# sy8502.net
KiCad netlist of a schematic drawn in Altium Designer
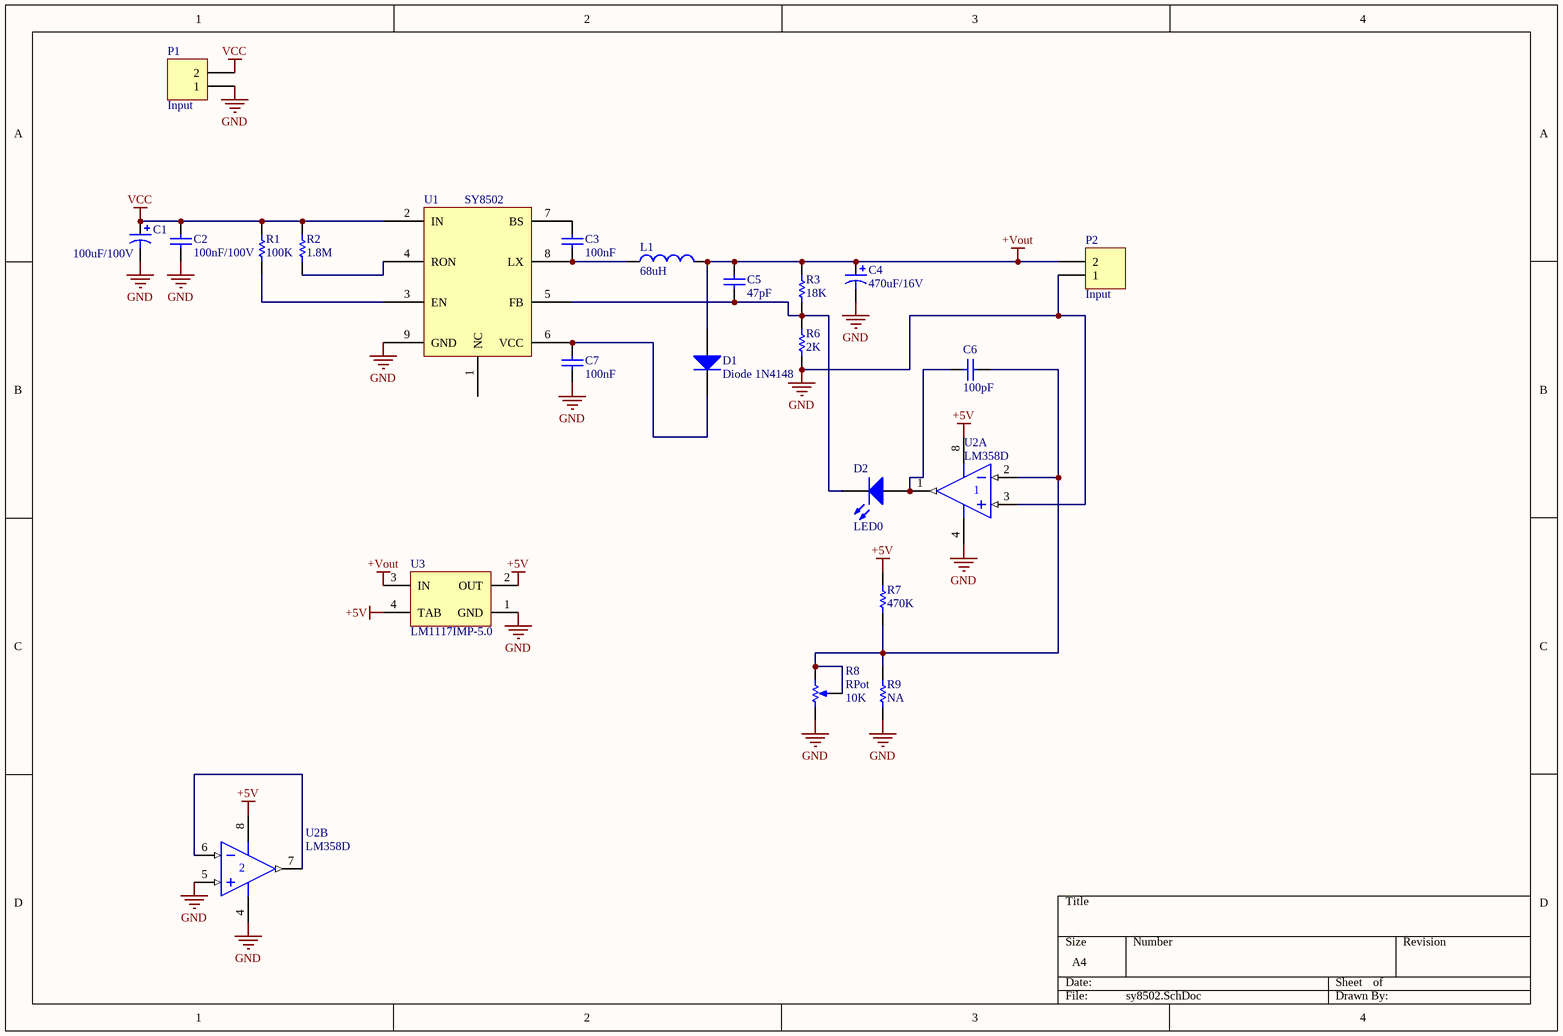
[diagram p0: sy8502.SchDoc]

(export (version "E")
  (design (tool "Eeschema 10.0.6"))
  (components
    (comp (ref "C1")
      (value "100uF/100V")
      (footprint "C_EL_8")
      (description "Polarized Capacitor (Radial)")
      (fields (field (name "PUBLISHER") "Altium Limited"))
      (libsource (lib "Miscellaneous Devices") (part "Cap Pol1"))
    )
    (comp (ref "C2")
      (value "100nF/100V")
      (footprint "1206-Cap-S")
      (description "Capacitor")
      (fields (field (name "PUBLISHER") "Altium Limited"))
      (libsource (lib "Miscellaneous Devices") (part "Cap"))
    )
    (comp (ref "C3")
      (value "100nF")
      (footprint "1206-Cap-S")
      (description "Capacitor")
      (fields (field (name "PUBLISHER") "Altium Limited"))
      (libsource (lib "Miscellaneous Devices") (part "Cap"))
    )
    (comp (ref "C4")
      (value "470uF/16V")
      (footprint "C_EL_8")
      (description "Polarized Capacitor (Radial)")
      (fields (field (name "PUBLISHER") "Altium Limited"))
      (libsource (lib "Miscellaneous Devices") (part "Cap Pol1"))
    )
    (comp (ref "C5")
      (value "47pF")
      (footprint "1206-Cap-S")
      (description "Capacitor")
      (fields (field (name "PUBLISHER") "Altium Limited"))
      (libsource (lib "Miscellaneous Devices") (part "Cap"))
    )
    (comp (ref "C6")
      (value "100pF")
      (footprint "1206-Cap-S")
      (description "Capacitor")
      (fields (field (name "PUBLISHER") "Altium Limited"))
      (libsource (lib "Miscellaneous Devices") (part "Cap"))
    )
    (comp (ref "C7")
      (value "100nF")
      (footprint "1206-Cap-S")
      (description "Capacitor")
      (fields (field (name "PUBLISHER") "Altium Limited"))
      (libsource (lib "Miscellaneous Devices") (part "Cap"))
    )
    (comp (ref "D1")
      (value "Diode 1N4148")
      (footprint "D1808")
      (description "High Conductance Fast Diode")
      (fields (field (name "PUBLISHER") "Altium Limited"))
      (libsource (lib "Miscellaneous Devices") (part "Diode 1N4148"))
    )
    (comp (ref "D2")
      (value "LED0")
      (footprint "LED1206GRN")
      (description "Typical INFRARED GaAs LED")
      (fields (field (name "PUBLISHER") "Altium Limited"))
      (libsource (lib "Miscellaneous Devices") (part "LED0"))
    )
    (comp (ref "L1")
      (value "68uH")
      (footprint "Bobin_smd_10*10")
      (description "Inductor")
      (fields (field (name "PUBLISHER") "Altium Limited"))
      (libsource (lib "Miscellaneous Devices") (part "Inductor"))
    )
    (comp (ref "P1")
      (value "Input")
      (footprint "HDR1X2")
      (description "Header, 2-Pin")
      (fields (field (name "PUBLISHER") "Altium Limited"))
      (libsource (lib "Miscellaneous Connectors") (part "Header 2"))
    )
    (comp (ref "P2")
      (value "Input")
      (footprint "HDR1X2")
      (description "Header, 2-Pin")
      (fields (field (name "PUBLISHER") "Altium Limited"))
      (libsource (lib "") (part "Header 2_1"))
    )
    (comp (ref "R1")
      (value "100K")
      (footprint "1206-Res-S")
      (description "Resistor")
      (fields (field (name "PUBLISHER") "Altium Limited"))
      (libsource (lib "Miscellaneous Devices") (part "Res1"))
    )
    (comp (ref "R2")
      (value "1.8M")
      (footprint "1206-Res-S")
      (description "Resistor")
      (fields (field (name "PUBLISHER") "Altium Limited"))
      (libsource (lib "Miscellaneous Devices") (part "Res1"))
    )
    (comp (ref "R3")
      (value "18K")
      (footprint "1206-Res-S")
      (description "Resistor")
      (fields (field (name "PUBLISHER") "Altium Limited"))
      (libsource (lib "Miscellaneous Devices") (part "Res1"))
    )
    (comp (ref "R6")
      (value "2K")
      (footprint "1206-Res-S")
      (description "Resistor")
      (fields (field (name "PUBLISHER") "Altium Limited"))
      (libsource (lib "Miscellaneous Devices") (part "Res1"))
    )
    (comp (ref "R7")
      (value "470K")
      (footprint "1206-Res-S")
      (description "Resistor")
      (fields (field (name "PUBLISHER") "Altium Limited"))
      (libsource (lib "Miscellaneous Devices") (part "Res1"))
    )
    (comp (ref "R8")
      (value "RPot")
      (footprint "POT_3296W")
      (description "Potentiometer")
      (fields (field (name "ALTIUM_VALUE") "10K") (field (name "PUBLISHER") "Altium Limited"))
      (libsource (lib "Miscellaneous Devices") (part "RPot"))
    )
    (comp (ref "R9")
      (value "NA")
      (footprint "1206-Res-S")
      (description "Resistor")
      (fields (field (name "PUBLISHER") "Altium Limited"))
      (libsource (lib "Miscellaneous Devices") (part "Res1"))
    )
    (comp (ref "U1")
      (value "SY8502")
      (footprint "SO_8T")
      (description "Step Down Regulator")
      (libsource (lib "2lphin") (part "SY8502"))
    )
    (comp (ref "U2")
      (value "LM358D")
      (footprint "SO_8")
      (description "Dual Low-Power Operational Amplifier")
      (fields (field (name "PUBLISHER") "Altium Limited"))
      (libsource (lib "Motorola Amplifier Operational Amplifier") (part "LM358D"))
    )
    (comp (ref "U3")
      (value "LM1117IMP-5.0")
      (footprint "SOT223_4")
      (description "800mA Low-Dropout Linear Regulator, 4-pin SOT-223")
      (fields
        (field (name "MANUFACTURER") "National Semiconductor")
        (field (name "PUBLISHER") "Altium Limited")
      )
      (libsource (lib "NSC LDO") (part "LM1117IMP-5.0"))
    )
  )
  (nets
    (net (code "1") (name "+5V") (class "Default")
      (node (ref "R7") (pin "2") (pinfunction "2_2") (pintype "passive"))
      (node (ref "U2") (pin "8") (pinfunction "V+_8") (pintype "power_in"))
      (node (ref "U3") (pin "2") (pinfunction "OUT_2") (pintype "power_in"))
      (node (ref "U3") (pin "4") (pinfunction "TAB_4") (pintype "power_in"))
    )
    (net (code "2") (name "+Vout") (class "Default")
      (node (ref "C4") (pin "1") (pinfunction "1_1") (pintype "passive"))
      (node (ref "C5") (pin "2") (pinfunction "2_2") (pintype "passive"))
      (node (ref "D1") (pin "1") (pinfunction "A_1") (pintype "passive"))
      (node (ref "L1") (pin "2") (pinfunction "2_2") (pintype "passive"))
      (node (ref "P2") (pin "2") (pinfunction "2_2") (pintype "passive"))
      (node (ref "R3") (pin "2") (pinfunction "2_2") (pintype "passive"))
      (node (ref "U3") (pin "3") (pinfunction "IN_3") (pintype "power_in"))
    )
    (net (code "3") (name "GND") (class "Default")
      (node (ref "C1") (pin "2") (pinfunction "2_2") (pintype "passive"))
      (node (ref "C2") (pin "1") (pinfunction "1_1") (pintype "passive"))
      (node (ref "C4") (pin "2") (pinfunction "2_2") (pintype "passive"))
      (node (ref "C7") (pin "1") (pinfunction "1_1") (pintype "passive"))
      (node (ref "P1") (pin "1") (pinfunction "1_1") (pintype "passive"))
      (node (ref "P2") (pin "1") (pinfunction "1_1") (pintype "passive"))
      (node (ref "R6") (pin "1") (pinfunction "1_1") (pintype "passive"))
      (node (ref "R8") (pin "1") (pinfunction "TOP_1") (pintype "passive"))
      (node (ref "R9") (pin "1") (pinfunction "1_1") (pintype "passive"))
      (node (ref "U1") (pin "9") (pinfunction "GND_9") (pintype "power_in"))
      (node (ref "U2") (pin "3") (pinfunction "IN+_3") (pintype "input"))
      (node (ref "U2") (pin "4") (pinfunction "V-_4") (pintype "power_in"))
      (node (ref "U2") (pin "5") (pinfunction "IN+_5") (pintype "input"))
      (node (ref "U3") (pin "1") (pinfunction "GND_1") (pintype "power_in"))
    )
    (net (code "4") (name "Net-(D1-K)") (class "Default")
      (node (ref "C7") (pin "2") (pinfunction "2_2") (pintype "passive"))
      (node (ref "D1") (pin "2") (pinfunction "K_2") (pintype "passive"))
      (node (ref "U1") (pin "6") (pinfunction "VCC_6") (pintype "power_in"))
    )
    (net (code "5") (name "Net-(D2-A)") (class "Default")
      (node (ref "C6") (pin "2") (pinfunction "2_2") (pintype "passive"))
      (node (ref "D2") (pin "1") (pinfunction "A_1") (pintype "passive"))
      (node (ref "U2") (pin "1") (pinfunction "OUT_1") (pintype "output"))
    )
    (net (code "6") (name "Net-(D2-K)") (class "Default")
      (node (ref "C5") (pin "1") (pinfunction "1_1") (pintype "passive"))
      (node (ref "D2") (pin "2") (pinfunction "K_2") (pintype "passive"))
      (node (ref "R3") (pin "1") (pinfunction "1_1") (pintype "passive"))
      (node (ref "R6") (pin "2") (pinfunction "2_2") (pintype "passive"))
      (node (ref "U1") (pin "5") (pinfunction "FB_5") (pintype "power_in"))
    )
    (net (code "7") (name "Net-(R8-BOT)") (class "Default")
      (node (ref "C6") (pin "1") (pinfunction "1_1") (pintype "passive"))
      (node (ref "R7") (pin "1") (pinfunction "1_1") (pintype "passive"))
      (node (ref "R8") (pin "2") (pinfunction "BOT_2") (pintype "passive"))
      (node (ref "R8") (pin "3") (pinfunction "TAP_3") (pintype "passive"))
      (node (ref "R9") (pin "2") (pinfunction "2_2") (pintype "passive"))
      (node (ref "U2") (pin "2") (pinfunction "IN-_2") (pintype "input"))
    )
    (net (code "8") (name "Net-(U1-BS)") (class "Default")
      (node (ref "C3") (pin "2") (pinfunction "2_2") (pintype "passive"))
      (node (ref "U1") (pin "7") (pinfunction "BS_7") (pintype "power_in"))
    )
    (net (code "9") (name "Net-(U1-EN)") (class "Default")
      (node (ref "R1") (pin "1") (pinfunction "1_1") (pintype "passive"))
      (node (ref "U1") (pin "3") (pinfunction "EN_3") (pintype "power_in"))
    )
    (net (code "10") (name "Net-(U1-LX)") (class "Default")
      (node (ref "C3") (pin "1") (pinfunction "1_1") (pintype "passive"))
      (node (ref "L1") (pin "1") (pinfunction "1_1") (pintype "passive"))
      (node (ref "U1") (pin "8") (pinfunction "LX_8") (pintype "power_in"))
    )
    (net (code "11") (name "Net-(U1-RON)") (class "Default")
      (node (ref "R2") (pin "1") (pinfunction "1_1") (pintype "passive"))
      (node (ref "U1") (pin "4") (pinfunction "RON_4") (pintype "power_in"))
    )
    (net (code "12") (name "Net-(U2B-IN-)") (class "Default")
      (node (ref "U2") (pin "6") (pinfunction "IN-_6") (pintype "input"))
      (node (ref "U2") (pin "7") (pinfunction "OUT_7") (pintype "output"))
    )
    (net (code "13") (name "VCC") (class "Default")
      (node (ref "C1") (pin "1") (pinfunction "1_1") (pintype "passive"))
      (node (ref "C2") (pin "2") (pinfunction "2_2") (pintype "passive"))
      (node (ref "P1") (pin "2") (pinfunction "2_2") (pintype "passive"))
      (node (ref "R1") (pin "2") (pinfunction "2_2") (pintype "passive"))
      (node (ref "R2") (pin "2") (pinfunction "2_2") (pintype "passive"))
      (node (ref "U1") (pin "2") (pinfunction "IN_2") (pintype "power_in"))
    )
    (net (code "14") (name "unconnected-(U1-NC-Pad1)") (class "Default")
      (node (ref "U1") (pin "1") (pinfunction "NC_1") (pintype "power_in"))
    )
  )
)
